# 03-WWVB_Path.net
KiCad netlist of a schematic drawn in Altium Designer
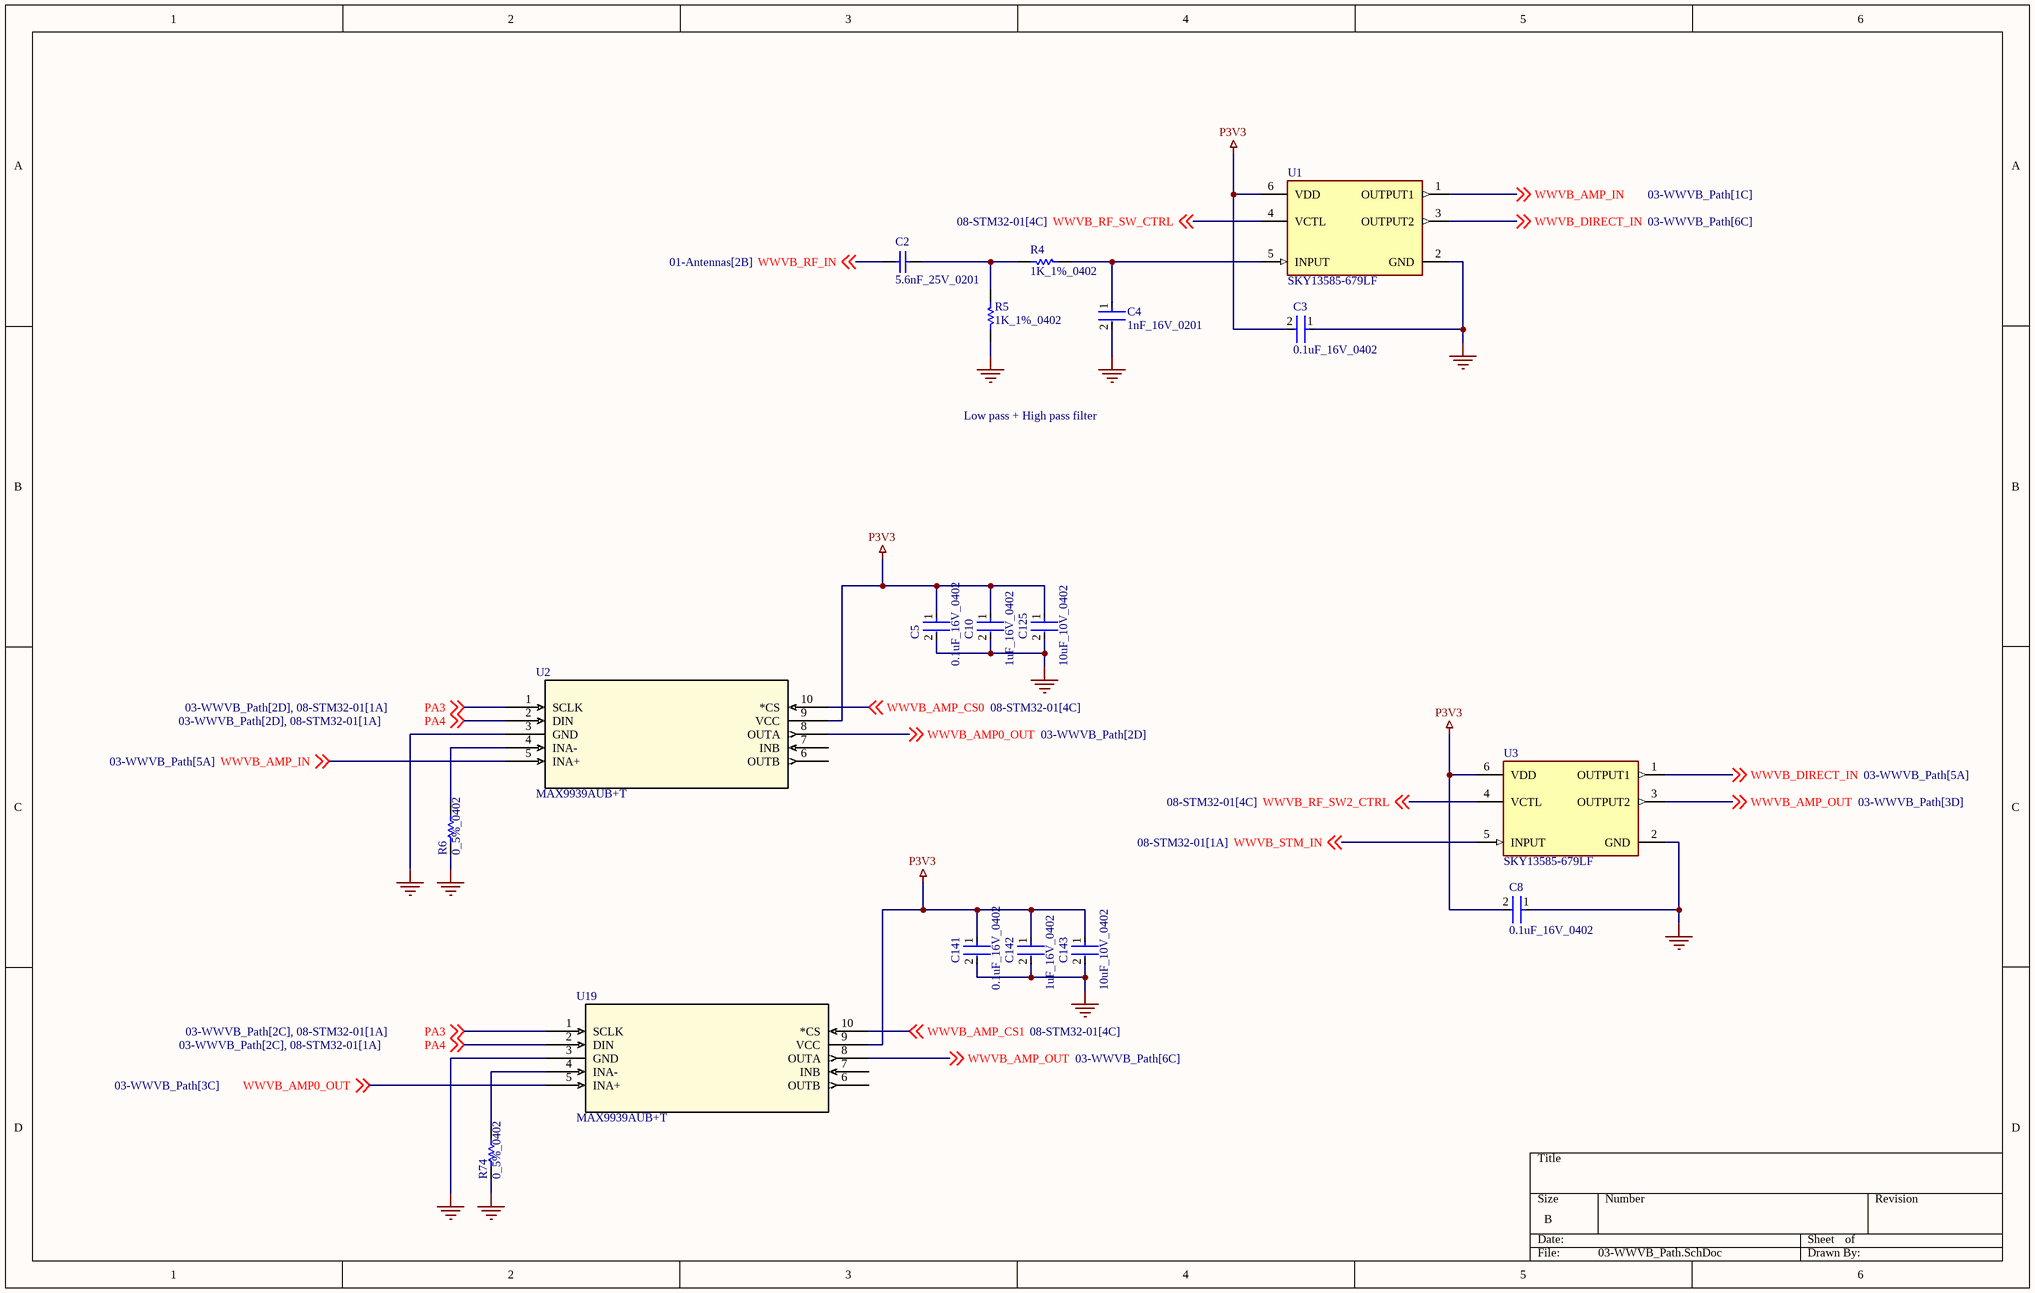
[diagram p0: 03-WWVB_Path.SchDoc]

(export (version "E")
  (design (tool "Eeschema 10.0.6"))
  (components
    (comp (ref "C2")
      (value "5.6nF_25V_0201")
      (footprint "CAPC0603X33X15ML03T05")
      (fields (field (name "PART NUMBER") "MC000322") (field (name "MANUFACTURER") "Multicomp"))
      (libsource (lib "Altium Content Vault") (part "CAP"))
    )
    (comp (ref "C3")
      (value "0.1uF_16V_0402")
      (footprint "FP-C0402-BB-MFG")
      (description "CAP CER 0.1UF 16V 5% X7R 0402")
      (fields
        (field (name "MANUFACTURER") "Kemet")
        (field (name "MANUFACTURER PART NUMBER") "C0402C104J4RACTU")
      )
      (libsource (lib "Altium Content Vault") (part "b4654b650e69147ec39a6b967a45e02"))
    )
    (comp (ref "C4")
      (value "1nF_16V_0201")
      (footprint "FP-0201-L_0_6_0_09-W_0_3-MFG")
      (description "General Purpose Ceramic Capacitor, 0201, 1nF, 10%, X7R, 15%, 16V")
      (fields (field (name "VOLTAGE") "16V") (field (name "TOLERANCE") "10%"))
      (libsource (lib "Altium Content Vault") (part "b4654b650e69147ec39a6b967a45e02"))
    )
    (comp (ref "C5")
      (value "0.1uF_16V_0402")
      (footprint "FP-C0402-BB-MFG")
      (description "CAP CER 0.1UF 16V 5% X7R 0402")
      (fields
        (field (name "MANUFACTURER") "Kemet")
        (field (name "MANUFACTURER PART NUMBER") "C0402C104J4RACTU")
      )
      (libsource (lib "Altium Content Vault") (part "b4654b650e69147ec39a6b967a45e02"))
    )
    (comp (ref "C8")
      (value "0.1uF_16V_0402")
      (footprint "FP-C0402-BB-MFG")
      (description "CAP CER 0.1UF 16V 5% X7R 0402")
      (fields
        (field (name "MANUFACTURER") "Kemet")
        (field (name "MANUFACTURER PART NUMBER") "C0402C104J4RACTU")
      )
      (libsource (lib "Altium Content Vault") (part "b4654b650e69147ec39a6b967a45e02"))
    )
    (comp (ref "C10")
      (value "1uF_16V_0402")
      (footprint "FP-0402-L_1_0_0_05-W_0_5-IPC_A")
      (description "None")
      (fields (field (name "TOLERANCE") "10%"))
      (libsource (lib "Altium Content Vault") (part "b4654b650e69147ec39a6b967a45e02"))
    )
    (comp (ref "C125")
      (value "10uF_10V_0402")
      (footprint "FP-CL05A106MP5NUNC-MFG")
      (description "CAP CER 10UF 10V X5R 0402")
      (fields
        (field (name "OCTOPART") "https://octopart.com/cl05a106mp5nunc-samsung-22457395")
        (field (name "TOLERANCE") "20%")
      )
      (libsource (lib "Altium Content Vault") (part "b4654b650e69147ec39a6b967a45e02"))
    )
    (comp (ref "C141")
      (value "0.1uF_16V_0402")
      (footprint "FP-C0402-BB-MFG")
      (description "CAP CER 0.1UF 16V 5% X7R 0402")
      (fields
        (field (name "MANUFACTURER") "Kemet")
        (field (name "MANUFACTURER PART NUMBER") "C0402C104J4RACTU")
      )
      (libsource (lib "Altium Content Vault") (part "b4654b650e69147ec39a6b967a45e02"))
    )
    (comp (ref "C142")
      (value "1uF_16V_0402")
      (footprint "FP-0402-L_1_0_0_05-W_0_5-IPC_A")
      (description "None")
      (fields (field (name "TOLERANCE") "10%"))
      (libsource (lib "Altium Content Vault") (part "b4654b650e69147ec39a6b967a45e02"))
    )
    (comp (ref "C143")
      (value "10uF_10V_0402")
      (footprint "FP-CL05A106MP5NUNC-MFG")
      (description "CAP CER 10UF 10V X5R 0402")
      (fields
        (field (name "OCTOPART") "https://octopart.com/cl05a106mp5nunc-samsung-22457395")
        (field (name "TOLERANCE") "20%")
      )
      (libsource (lib "Altium Content Vault") (part "b4654b650e69147ec39a6b967a45e02"))
    )
    (comp (ref "R4")
      (value "1K_1%_0402")
      (footprint "RESC1005X40X25NL05T05")
      (fields (field (name "MANUFACTURER") "Vishay Dale") (field (name "PART NUMBER") "CRCW04021K00FKTD"))
      (libsource (lib "Altium Content Vault") (part "RES"))
    )
    (comp (ref "R5")
      (value "1K_1%_0402")
      (footprint "RESC1005X40X25NL05T05")
      (fields (field (name "MANUFACTURER") "Vishay Dale") (field (name "PART NUMBER") "CRCW04021K00FKTD"))
      (libsource (lib "Altium Content Vault") (part "RES"))
    )
    (comp (ref "R6")
      (value "0_5%_0402")
      (footprint "RESC1005X40X25NL05T10")
      (fields (field (name "MANUFACTURER") "Panasonic") (field (name "PART NUMBER") "ERJ-U020R00X"))
      (libsource (lib "Altium Content Vault") (part "RES"))
    )
    (comp (ref "R74")
      (value "0_5%_0402")
      (footprint "RESC1005X40X25NL05T10")
      (fields (field (name "MANUFACTURER") "Panasonic") (field (name "PART NUMBER") "ERJ-U020R00X"))
      (libsource (lib "Altium Content Vault") (part "RES"))
    )
    (comp (ref "U1")
      (value "SKY13585-679LF")
      (footprint "FP-SKY13585-679LF-MFG")
      (description "IC RF SWITCH SPDT 6GHZ 6MLPD")
      (libsource (lib "Altium Content Vault") (part "e67e48af39ab44f3294fce00d3e4f12"))
    )
    (comp (ref "U2")
      (value "MAX9939AUB+T")
      (footprint "21-0061L_MXM")
      (description "No Description Available")
      (fields (field (name "COPYRIGHT") "Copyright (C) 2023 Ultra Librarian. All rights reserved."))
      (libsource (lib "MAX9939AUB&plus_T") (part "MAX9939AUB+T"))
    )
    (comp (ref "U3")
      (value "SKY13585-679LF")
      (footprint "FP-SKY13585-679LF-MFG")
      (description "IC RF SWITCH SPDT 6GHZ 6MLPD")
      (libsource (lib "Altium Content Vault") (part "e67e48af39ab44f3294fce00d3e4f12"))
    )
    (comp (ref "U19")
      (value "MAX9939AUB+T")
      (footprint "21-0061L_MXM")
      (description "No Description Available")
      (fields (field (name "COPYRIGHT") "Copyright (C) 2023 Ultra Librarian. All rights reserved."))
      (libsource (lib "MAX9939AUB&plus_T") (part "MAX9939AUB+T"))
    )
  )
  (nets
    (net (code "1") (name "GND") (class "Default")
      (node (ref "C10") (pin "2") (pinfunction "2_2") (pintype "passive"))
      (node (ref "C125") (pin "2") (pinfunction "2_2") (pintype "passive"))
      (node (ref "C141") (pin "2") (pinfunction "2_2") (pintype "passive"))
      (node (ref "C142") (pin "2") (pinfunction "2_2") (pintype "passive"))
      (node (ref "C143") (pin "2") (pinfunction "2_2") (pintype "passive"))
      (node (ref "C3") (pin "1") (pinfunction "1_1") (pintype "passive"))
      (node (ref "C4") (pin "2") (pinfunction "2_2") (pintype "passive"))
      (node (ref "C5") (pin "2") (pinfunction "2_2") (pintype "passive"))
      (node (ref "C8") (pin "1") (pinfunction "1_1") (pintype "passive"))
      (node (ref "R5") (pin "1") (pinfunction "1_1") (pintype "passive"))
      (node (ref "R6") (pin "1") (pinfunction "1_1") (pintype "passive"))
      (node (ref "R74") (pin "1") (pinfunction "1_1") (pintype "passive"))
      (node (ref "U1") (pin "2") (pinfunction "GND_2") (pintype "power_in"))
      (node (ref "U19") (pin "3") (pinfunction "GND_3") (pintype "power_in"))
      (node (ref "U2") (pin "3") (pinfunction "GND_3") (pintype "power_in"))
      (node (ref "U3") (pin "2") (pinfunction "GND_2") (pintype "power_in"))
    )
    (net (code "2") (name "Net-(C2-Pad2)") (class "Default")
      (node (ref "C2") (pin "2") (pinfunction "2_2") (pintype "passive"))
      (node (ref "R4") (pin "2") (pinfunction "2_2") (pintype "passive"))
      (node (ref "R5") (pin "2") (pinfunction "2_2") (pintype "passive"))
    )
    (net (code "3") (name "Net-(U1-INPUT)") (class "Default")
      (node (ref "C4") (pin "1") (pinfunction "1_1") (pintype "passive"))
      (node (ref "R4") (pin "1") (pinfunction "1_1") (pintype "passive"))
      (node (ref "U1") (pin "5") (pinfunction "INPUT_5") (pintype "input"))
    )
    (net (code "4") (name "Net-(U2-INA-)") (class "Default")
      (node (ref "R6") (pin "2") (pinfunction "2_2") (pintype "passive"))
      (node (ref "U2") (pin "4") (pinfunction "INA-_4") (pintype "input"))
    )
    (net (code "5") (name "Net-(U19-INA-)") (class "Default")
      (node (ref "R74") (pin "2") (pinfunction "2_2") (pintype "passive"))
      (node (ref "U19") (pin "4") (pinfunction "INA-_4") (pintype "input"))
    )
    (net (code "6") (name "P3V3") (class "Default")
      (node (ref "C10") (pin "1") (pinfunction "1_1") (pintype "passive"))
      (node (ref "C125") (pin "1") (pinfunction "1_1") (pintype "passive"))
      (node (ref "C141") (pin "1") (pinfunction "1_1") (pintype "passive"))
      (node (ref "C142") (pin "1") (pinfunction "1_1") (pintype "passive"))
      (node (ref "C143") (pin "1") (pinfunction "1_1") (pintype "passive"))
      (node (ref "C3") (pin "2") (pinfunction "2_2") (pintype "passive"))
      (node (ref "C5") (pin "1") (pinfunction "1_1") (pintype "passive"))
      (node (ref "C8") (pin "2") (pinfunction "2_2") (pintype "passive"))
      (node (ref "U1") (pin "6") (pinfunction "VDD_6") (pintype "power_in"))
      (node (ref "U19") (pin "9") (pinfunction "VCC_9") (pintype "power_in"))
      (node (ref "U2") (pin "9") (pinfunction "VCC_9") (pintype "power_in"))
      (node (ref "U3") (pin "6") (pinfunction "VDD_6") (pintype "power_in"))
    )
    (net (code "7") (name "PA3") (class "Default")
      (node (ref "U19") (pin "1") (pinfunction "SCLK_1") (pintype "input"))
      (node (ref "U2") (pin "1") (pinfunction "SCLK_1") (pintype "input"))
    )
    (net (code "8") (name "PA4") (class "Default")
      (node (ref "U19") (pin "2") (pinfunction "DIN_2") (pintype "input"))
      (node (ref "U2") (pin "2") (pinfunction "DIN_2") (pintype "input"))
    )
    (net (code "9") (name "WWVB_AMP0_OUT") (class "Default")
      (node (ref "U19") (pin "5") (pinfunction "INA+_5") (pintype "input"))
      (node (ref "U2") (pin "8") (pinfunction "OUTA_8") (pintype "output"))
    )
    (net (code "10") (name "WWVB_AMP_CS0") (class "Default")
      (node (ref "U2") (pin "10") (pinfunction "*CS_10") (pintype "input"))
    )
    (net (code "11") (name "WWVB_AMP_CS1") (class "Default")
      (node (ref "U19") (pin "10") (pinfunction "*CS_10") (pintype "input"))
    )
    (net (code "12") (name "WWVB_AMP_IN") (class "Default")
      (node (ref "U1") (pin "1") (pinfunction "OUTPUT1_1") (pintype "output"))
      (node (ref "U2") (pin "5") (pinfunction "INA+_5") (pintype "input"))
    )
    (net (code "13") (name "WWVB_AMP_OUT") (class "Default")
      (node (ref "U19") (pin "8") (pinfunction "OUTA_8") (pintype "output"))
      (node (ref "U3") (pin "3") (pinfunction "OUTPUT2_3") (pintype "output"))
    )
    (net (code "14") (name "WWVB_DIRECT_IN") (class "Default")
      (node (ref "U1") (pin "3") (pinfunction "OUTPUT2_3") (pintype "output"))
      (node (ref "U3") (pin "1") (pinfunction "OUTPUT1_1") (pintype "output"))
    )
    (net (code "15") (name "WWVB_RF_IN") (class "Default")
      (node (ref "C2") (pin "1") (pinfunction "1_1") (pintype "passive"))
    )
    (net (code "16") (name "WWVB_RF_SW2_CTRL") (class "Default")
      (node (ref "U3") (pin "4") (pinfunction "VCTL_4") (pintype "power_in"))
    )
    (net (code "17") (name "WWVB_RF_SW_CTRL") (class "Default")
      (node (ref "U1") (pin "4") (pinfunction "VCTL_4") (pintype "power_in"))
    )
    (net (code "18") (name "WWVB_STM_IN") (class "Default")
      (node (ref "U3") (pin "5") (pinfunction "INPUT_5") (pintype "input"))
    )
    (net (code "19") (name "unconnected-(U2-INB-Pad7)") (class "Default")
      (node (ref "U2") (pin "7") (pinfunction "INB_7") (pintype "input"))
    )
    (net (code "20") (name "unconnected-(U2-OUTB-Pad6)") (class "Default")
      (node (ref "U2") (pin "6") (pinfunction "OUTB_6") (pintype "output"))
    )
    (net (code "21") (name "unconnected-(U19-INB-Pad7)") (class "Default")
      (node (ref "U19") (pin "7") (pinfunction "INB_7") (pintype "input"))
    )
    (net (code "22") (name "unconnected-(U19-OUTB-Pad6)") (class "Default")
      (node (ref "U19") (pin "6") (pinfunction "OUTB_6") (pintype "output"))
    )
  )
)
